# sma-to-bnc-feedthrough-v3.net
KiCad netlist of a schematic drawn in EAGLE
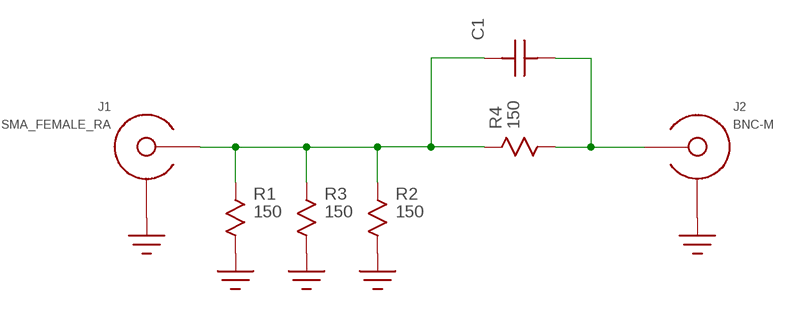
[diagram p0: schematic, sheet 1]

(export (version "E")
  (design (tool "Eeschema 10.0.6"))
  (components
    (comp (ref "C1")
      (value "C0603")
      (footprint "eagle-import:C0603")
      (libsource (lib "eagle-import") (part "C0603"))
    )
    (comp (ref "J1")
      (value "SMA_FEMALE_RA")
      (footprint "eagle-import:SMA_RA_PCB")
      (libsource (lib "eagle-import") (part "SMA_FEMALE_RA"))
    )
    (comp (ref "J2")
      (value "BNC-M")
      (footprint "eagle-import:BNC_MALE_PCB")
      (libsource (lib "eagle-import") (part "BNC_MALE_PCB"))
    )
    (comp (ref "R1")
      (value "150")
      (footprint "eagle-import:R0603")
      (libsource (lib "eagle-import") (part "R0603"))
    )
    (comp (ref "R2")
      (value "150")
      (footprint "eagle-import:R0603")
      (libsource (lib "eagle-import") (part "R0603"))
    )
    (comp (ref "R3")
      (value "150")
      (footprint "eagle-import:R0603")
      (libsource (lib "eagle-import") (part "R0603"))
    )
    (comp (ref "R4")
      (value "150")
      (footprint "eagle-import:R0603")
      (libsource (lib "eagle-import") (part "R0603"))
    )
  )
  (nets
    (net (code "1") (name "GND") (class "Default")
      (node (ref "J1") (pin "SHIELD@1") (pinfunction "SHIELD_SHIELD@1") (pintype "bidirectional"))
      (node (ref "J1") (pin "SHIELD@2") (pinfunction "SHIELD_SHIELD@2") (pintype "bidirectional"))
      (node (ref "J1") (pin "SHIELD@3") (pinfunction "SHIELD_SHIELD@3") (pintype "bidirectional"))
      (node (ref "J1") (pin "SHIELD@4") (pinfunction "SHIELD_SHIELD@4") (pintype "bidirectional"))
      (node (ref "J2") (pin "SHIELD@1") (pinfunction "SHIELD_SHIELD@1") (pintype "bidirectional"))
      (node (ref "J2") (pin "SHIELD@2") (pinfunction "SHIELD_SHIELD@2") (pintype "bidirectional"))
      (node (ref "J2") (pin "SHIELD@3") (pinfunction "SHIELD_SHIELD@3") (pintype "bidirectional"))
      (node (ref "J2") (pin "SHIELD@4") (pinfunction "SHIELD_SHIELD@4") (pintype "bidirectional"))
      (node (ref "R1") (pin "P$2") (pinfunction "P$4_P$2") (pintype "bidirectional"))
      (node (ref "R2") (pin "P$2") (pinfunction "P$4_P$2") (pintype "bidirectional"))
      (node (ref "R3") (pin "P$2") (pinfunction "P$4_P$2") (pintype "bidirectional"))
    )
    (net (code "2") (name "Net-(R1-P$3)") (class "Default")
      (node (ref "C1") (pin "P$2") (pinfunction "P$2_P$2") (pintype "bidirectional"))
      (node (ref "J1") (pin "CENTER") (pinfunction "CENTER_CENTER") (pintype "bidirectional"))
      (node (ref "R1") (pin "P$1") (pinfunction "P$3_P$1") (pintype "bidirectional"))
      (node (ref "R2") (pin "P$1") (pinfunction "P$3_P$1") (pintype "bidirectional"))
      (node (ref "R3") (pin "P$1") (pinfunction "P$3_P$1") (pintype "bidirectional"))
      (node (ref "R4") (pin "P$1") (pinfunction "P$3_P$1") (pintype "bidirectional"))
    )
    (net (code "3") (name "Net-(R4-P$4)") (class "Default")
      (node (ref "C1") (pin "P$1") (pinfunction "P$1_P$1") (pintype "bidirectional"))
      (node (ref "J2") (pin "CENTER") (pinfunction "CENTER_CENTER") (pintype "bidirectional"))
      (node (ref "R4") (pin "P$2") (pinfunction "P$4_P$2") (pintype "bidirectional"))
    )
  )
)
